# DE-080717.net
KiCad netlist of a schematic drawn in Altium Designer
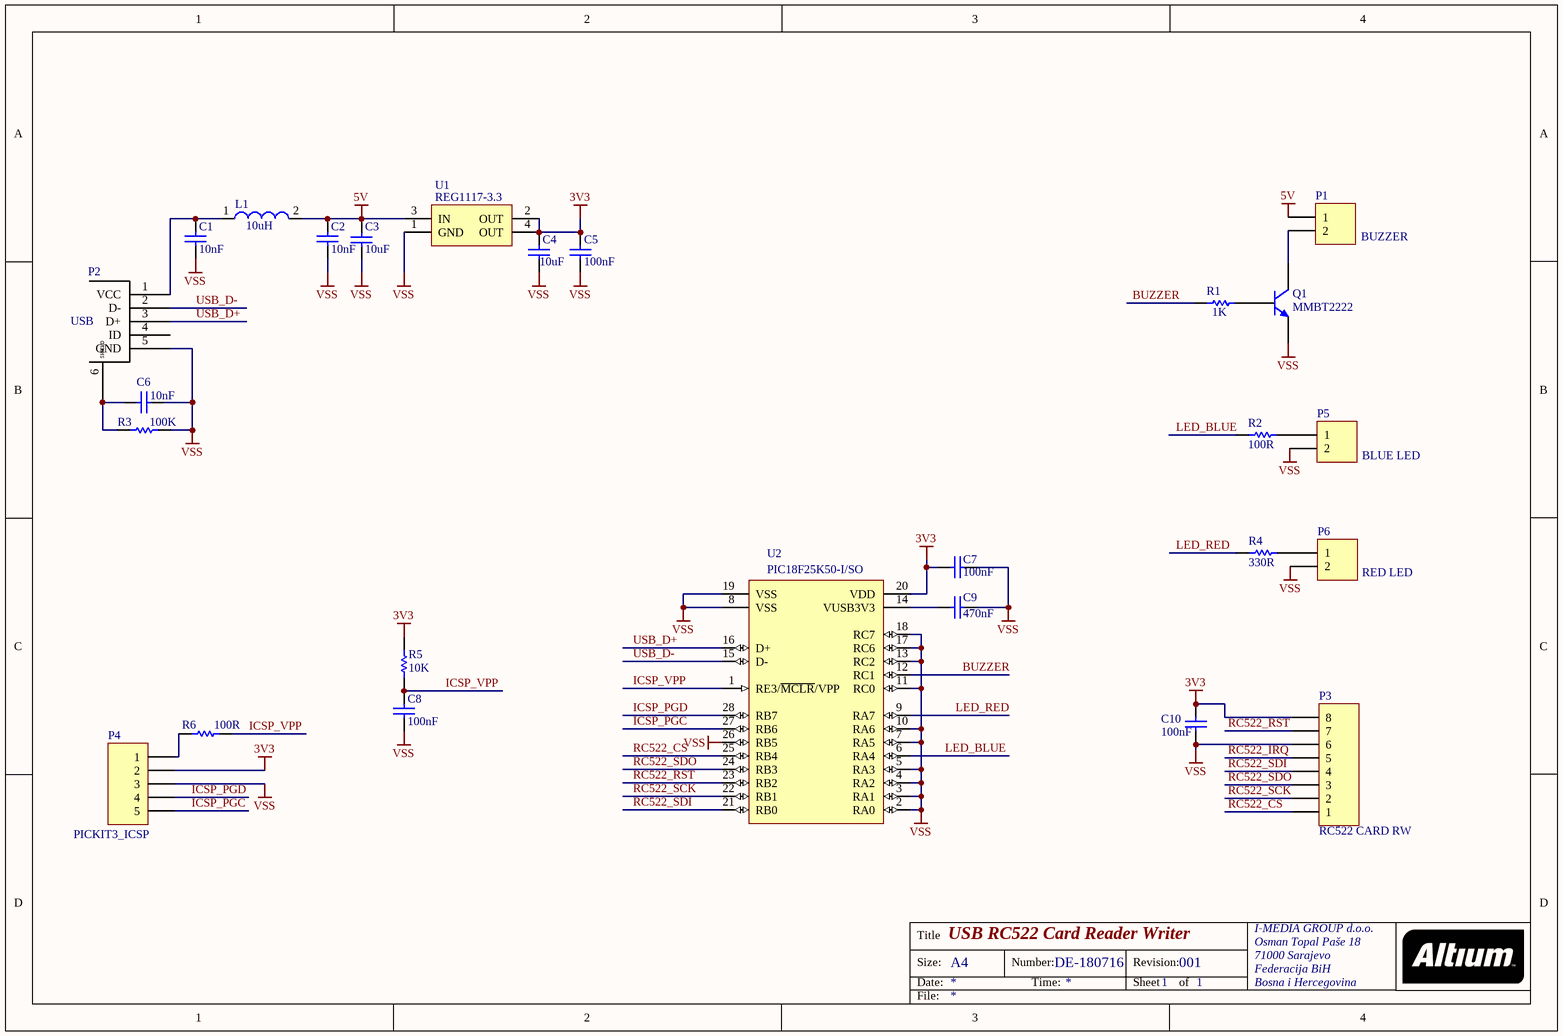
[diagram p0: DE-080717.SchDoc]

(export (version "E")
  (design (tool "Eeschema 10.0.6"))
  (components
    (comp (ref "C1")
      (value "10nF")
      (footprint "0603")
      (description "Ceramic Chip Capacitor - Standard")
      (fields (field (name "PUBLISHER") "Altium Limited"))
      (libsource (lib "USB_RC522_CARD_RW") (part "C0603"))
    )
    (comp (ref "C2")
      (value "10nF")
      (footprint "0603")
      (description "Ceramic Chip Capacitor - Standard")
      (fields (field (name "PUBLISHER") "Altium Limited"))
      (libsource (lib "USB_RC522_CARD_RW") (part "C0603"))
    )
    (comp (ref "C3")
      (value "10uF")
      (footprint "0805")
      (description "Ceramic Chip Capacitor - Standard")
      (fields (field (name "PUBLISHER") "Altium Limited"))
      (libsource (lib "USB_RC522_CARD_RW") (part "C0805"))
    )
    (comp (ref "C4")
      (value "10uF")
      (footprint "0805")
      (description "Ceramic Chip Capacitor - Standard")
      (fields (field (name "PUBLISHER") "Altium Limited"))
      (libsource (lib "USB_RC522_CARD_RW") (part "C0805"))
    )
    (comp (ref "C5")
      (value "100nF")
      (footprint "0603")
      (description "Ceramic Chip Capacitor - Standard")
      (fields (field (name "PUBLISHER") "Altium Limited"))
      (libsource (lib "USB_RC522_CARD_RW") (part "C0603"))
    )
    (comp (ref "C6")
      (value "10nF")
      (footprint "0603")
      (description "Ceramic Chip Capacitor - Standard")
      (fields (field (name "PUBLISHER") "Altium Limited"))
      (libsource (lib "USB_RC522_CARD_RW") (part "C0603"))
    )
    (comp (ref "C7")
      (value "100nF")
      (footprint "0603")
      (description "Ceramic Chip Capacitor - Standard")
      (fields (field (name "PUBLISHER") "Altium Limited"))
      (libsource (lib "USB_RC522_CARD_RW") (part "C0603"))
    )
    (comp (ref "C8")
      (value "100nF")
      (footprint "0603")
      (description "Ceramic Chip Capacitor - Standard")
      (fields (field (name "PUBLISHER") "Altium Limited"))
      (libsource (lib "USB_RC522_CARD_RW") (part "C0603"))
    )
    (comp (ref "C9")
      (value "470nF")
      (footprint "0805")
      (description "Ceramic Chip Capacitor - Standard")
      (fields (field (name "PUBLISHER") "Altium Limited"))
      (libsource (lib "USB_RC522_CARD_RW") (part "C0805"))
    )
    (comp (ref "C10")
      (value "100nF")
      (footprint "0603")
      (description "Ceramic Chip Capacitor - Standard")
      (fields (field (name "PUBLISHER") "Altium Limited"))
      (libsource (lib "USB_RC522_CARD_RW") (part "C0603"))
    )
    (comp (ref "L1")
      (value "10uH")
      (footprint "SMD-0805")
      (description "SMD-Multilayer Inductor WE-MI, L = 8.20 µH")
      (libsource (lib "USB_RC522_CARD_RW") (part "744790282"))
    )
    (comp (ref "P1")
      (value "BUZZER")
      (footprint "HDR1X2")
      (description "Header, 2-Pin")
      (fields (field (name "PUBLISHER") "Altium Limited"))
      (libsource (lib "USB_RC522_CARD_RW") (part "Header 2"))
    )
    (comp (ref "P2")
      (value "USB")
      (footprint "USB mini B")
      (description "USB connector B mini")
      (libsource (lib "USB_RC522_CARD_RW") (part "USB mini B"))
    )
    (comp (ref "P3")
      (value "RC522 CARD RW")
      (footprint "HDR1X8")
      (description "Header, 8-Pin")
      (fields (field (name "PUBLISHER") "Altium Limited"))
      (libsource (lib "USB_RC522_CARD_RW") (part "Header 8"))
    )
    (comp (ref "P4")
      (value "PICKIT3_ICSP")
      (footprint "HDR1X5")
      (description "Header, 5-Pin")
      (fields (field (name "PUBLISHER") "Altium Limited"))
      (libsource (lib "USB_RC522_CARD_RW") (part "Header 5"))
    )
    (comp (ref "P5")
      (value "BLUE LED")
      (footprint "HDR1X2")
      (description "Header, 2-Pin")
      (fields (field (name "PUBLISHER") "Altium Limited"))
      (libsource (lib "USB_RC522_CARD_RW") (part "Header 2"))
    )
    (comp (ref "P6")
      (value "RED LED")
      (footprint "HDR1X2")
      (description "Header, 2-Pin")
      (fields (field (name "PUBLISHER") "Altium Limited"))
      (libsource (lib "USB_RC522_CARD_RW") (part "Header 2"))
    )
    (comp (ref "Q1")
      (value "MMBT2222")
      (footprint "SOT23_N")
      (description "NPN General-purpose Transistor")
      (fields (field (name "PUBLISHER") "Altium Limited"))
      (libsource (lib "USB_RC522_CARD_RW") (part "BC817"))
    )
    (comp (ref "R1")
      (value "1K")
      (footprint "ERA-0603")
      (fields (field (name "PUBLISHER") "Altium Limited"))
      (libsource (lib "USB_RC522_CARD_RW") (part "ERAV"))
    )
    (comp (ref "R2")
      (value "100R")
      (footprint "ERA-0603")
      (fields (field (name "PUBLISHER") "Altium Limited"))
      (libsource (lib "USB_RC522_CARD_RW") (part "ERAV"))
    )
    (comp (ref "R3")
      (value "100K")
      (footprint "ERA-0603")
      (fields (field (name "PUBLISHER") "Altium Limited"))
      (libsource (lib "USB_RC522_CARD_RW") (part "ERAV"))
    )
    (comp (ref "R4")
      (value "330R")
      (footprint "ERA-0603")
      (fields (field (name "PUBLISHER") "Altium Limited"))
      (libsource (lib "USB_RC522_CARD_RW") (part "ERAV"))
    )
    (comp (ref "R5")
      (value "10K")
      (footprint "ERA-0603")
      (fields (field (name "PUBLISHER") "Altium Limited"))
      (libsource (lib "USB_RC522_CARD_RW") (part "ERAV"))
    )
    (comp (ref "R6")
      (value "100R")
      (footprint "ERA-0603")
      (fields (field (name "PUBLISHER") "Altium Limited"))
      (libsource (lib "USB_RC522_CARD_RW") (part "ERAV"))
    )
    (comp (ref "U1")
      (value "REG1117-3.3")
      (footprint "ZZ311")
      (description "800mA and 1A Low Dropout Positive Regulator 2.85V, 3.3V, 5V, and Adjustable")
      (fields (field (name "PUBLISHER") "Altium Limited"))
      (libsource (lib "USB_RC522_CARD_RW") (part "REG1117-3.3"))
    )
    (comp (ref "U2")
      (value "PIC18F25K50-I/SO")
      (footprint "MCHP-SOIC-SO28_N")
      (fields (field (name "MANUFACTURER") "Microchip"))
      (libsource (lib "Microchip PIC18") (part "PIC18F25K50-I/SO"))
    )
  )
  (nets
    (net (code "1") (name "/BUZZER") (class "Default")
      (node (ref "R1") (pin "1") (pinfunction "1_1") (pintype "passive"))
      (node (ref "U2") (pin "12") (pinfunction "RC1_12") (pintype "bidirectional"))
    )
    (net (code "2") (name "/ICSP_PGC") (class "Default")
      (node (ref "P4") (pin "5") (pinfunction "5_5") (pintype "passive"))
      (node (ref "U2") (pin "27") (pinfunction "RB6_27") (pintype "bidirectional"))
    )
    (net (code "3") (name "/ICSP_PGD") (class "Default")
      (node (ref "P4") (pin "4") (pinfunction "4_4") (pintype "passive"))
      (node (ref "U2") (pin "28") (pinfunction "RB7_28") (pintype "bidirectional"))
    )
    (net (code "4") (name "/ICSP_VPP") (class "Default")
      (node (ref "C8") (pin "1") (pinfunction "1_1") (pintype "passive"))
      (node (ref "R5") (pin "1") (pinfunction "1_1") (pintype "passive"))
      (node (ref "R6") (pin "1") (pinfunction "1_1") (pintype "passive"))
      (node (ref "U2") (pin "1") (pinfunction "RE3/~{MCLR}/VPP_1") (pintype "input"))
    )
    (net (code "5") (name "/LED_BLUE") (class "Default")
      (node (ref "R2") (pin "1") (pinfunction "1_1") (pintype "passive"))
      (node (ref "U2") (pin "6") (pinfunction "RA4_6") (pintype "bidirectional"))
    )
    (net (code "6") (name "/LED_RED") (class "Default")
      (node (ref "R4") (pin "1") (pinfunction "1_1") (pintype "passive"))
      (node (ref "U2") (pin "9") (pinfunction "RA7_9") (pintype "bidirectional"))
    )
    (net (code "7") (name "/RC522_CS") (class "Default")
      (node (ref "P3") (pin "1") (pinfunction "1_1") (pintype "passive"))
      (node (ref "U2") (pin "25") (pinfunction "RB4_25") (pintype "bidirectional"))
    )
    (net (code "8") (name "/RC522_IRQ") (class "Default")
      (node (ref "P3") (pin "5") (pinfunction "5_5") (pintype "passive"))
    )
    (net (code "9") (name "/RC522_RST") (class "Default")
      (node (ref "P3") (pin "7") (pinfunction "7_7") (pintype "passive"))
      (node (ref "U2") (pin "23") (pinfunction "RB2_23") (pintype "bidirectional"))
    )
    (net (code "10") (name "/RC522_SCK") (class "Default")
      (node (ref "P3") (pin "2") (pinfunction "2_2") (pintype "passive"))
      (node (ref "U2") (pin "22") (pinfunction "RB1_22") (pintype "bidirectional"))
    )
    (net (code "11") (name "/RC522_SDI") (class "Default")
      (node (ref "P3") (pin "4") (pinfunction "4_4") (pintype "passive"))
      (node (ref "U2") (pin "21") (pinfunction "RB0_21") (pintype "bidirectional"))
    )
    (net (code "12") (name "/RC522_SDO") (class "Default")
      (node (ref "P3") (pin "3") (pinfunction "3_3") (pintype "passive"))
      (node (ref "U2") (pin "24") (pinfunction "RB3_24") (pintype "bidirectional"))
    )
    (net (code "13") (name "/USB_D+") (class "Default")
      (node (ref "P2") (pin "3") (pinfunction "D+_3") (pintype "passive"))
      (node (ref "U2") (pin "16") (pinfunction "D+_16") (pintype "bidirectional"))
    )
    (net (code "14") (name "/USB_D-") (class "Default")
      (node (ref "P2") (pin "2") (pinfunction "D-_2") (pintype "passive"))
      (node (ref "U2") (pin "15") (pinfunction "D-_15") (pintype "bidirectional"))
    )
    (net (code "15") (name "3V3") (class "Default")
      (node (ref "C10") (pin "1") (pinfunction "1_1") (pintype "passive"))
      (node (ref "C4") (pin "2") (pinfunction "2_2") (pintype "passive"))
      (node (ref "C5") (pin "2") (pinfunction "2_2") (pintype "passive"))
      (node (ref "C7") (pin "2") (pinfunction "2_2") (pintype "passive"))
      (node (ref "P3") (pin "8") (pinfunction "8_8") (pintype "passive"))
      (node (ref "P4") (pin "2") (pinfunction "2_2") (pintype "passive"))
      (node (ref "R5") (pin "2") (pinfunction "2_2") (pintype "passive"))
      (node (ref "U1") (pin "2") (pinfunction "OUT_2") (pintype "power_in"))
      (node (ref "U1") (pin "4") (pinfunction "OUT_4") (pintype "power_in"))
      (node (ref "U2") (pin "20") (pinfunction "VDD_20") (pintype "power_in"))
    )
    (net (code "16") (name "5V") (class "Default")
      (node (ref "C2") (pin "1") (pinfunction "1_1") (pintype "passive"))
      (node (ref "C3") (pin "1") (pinfunction "1_1") (pintype "passive"))
      (node (ref "L1") (pin "2") (pinfunction "2_2") (pintype "passive"))
      (node (ref "P1") (pin "1") (pinfunction "1_1") (pintype "passive"))
      (node (ref "U1") (pin "3") (pinfunction "IN_3") (pintype "power_in"))
    )
    (net (code "17") (name "Net-(P2-SHIELD)") (class "Default")
      (node (ref "C6") (pin "1") (pinfunction "1_1") (pintype "passive"))
      (node (ref "P2") (pin "6") (pinfunction "SHIELD_6") (pintype "passive"))
      (node (ref "R3") (pin "2") (pinfunction "2_2") (pintype "passive"))
    )
    (net (code "18") (name "Net-(P2-VCC)") (class "Default")
      (node (ref "C1") (pin "1") (pinfunction "1_1") (pintype "passive"))
      (node (ref "L1") (pin "1") (pinfunction "1_1") (pintype "passive"))
      (node (ref "P2") (pin "1") (pinfunction "VCC_1") (pintype "passive"))
    )
    (net (code "19") (name "Net-(P4-Pad1)") (class "Default")
      (node (ref "P4") (pin "1") (pinfunction "1_1") (pintype "passive"))
      (node (ref "R6") (pin "2") (pinfunction "2_2") (pintype "passive"))
    )
    (net (code "20") (name "Net-(P5-Pad1)") (class "Default")
      (node (ref "P5") (pin "1") (pinfunction "1_1") (pintype "passive"))
      (node (ref "R2") (pin "2") (pinfunction "2_2") (pintype "passive"))
    )
    (net (code "21") (name "Net-(P6-Pad1)") (class "Default")
      (node (ref "P6") (pin "1") (pinfunction "1_1") (pintype "passive"))
      (node (ref "R4") (pin "2") (pinfunction "2_2") (pintype "passive"))
    )
    (net (code "22") (name "Net-(Q1-B)") (class "Default")
      (node (ref "Q1") (pin "1") (pinfunction "B_1") (pintype "passive"))
      (node (ref "R1") (pin "2") (pinfunction "2_2") (pintype "passive"))
    )
    (net (code "23") (name "Net-(Q1-C)") (class "Default")
      (node (ref "P1") (pin "2") (pinfunction "2_2") (pintype "passive"))
      (node (ref "Q1") (pin "3") (pinfunction "C_3") (pintype "passive"))
    )
    (net (code "24") (name "Net-(U2-VUSB3V3)") (class "Default")
      (node (ref "C9") (pin "2") (pinfunction "2_2") (pintype "passive"))
      (node (ref "U2") (pin "14") (pinfunction "VUSB3V3_14") (pintype "power_in"))
    )
    (net (code "25") (name "VSS") (class "Default")
      (node (ref "C1") (pin "2") (pinfunction "2_2") (pintype "passive"))
      (node (ref "C10") (pin "2") (pinfunction "2_2") (pintype "passive"))
      (node (ref "C2") (pin "2") (pinfunction "2_2") (pintype "passive"))
      (node (ref "C3") (pin "2") (pinfunction "2_2") (pintype "passive"))
      (node (ref "C4") (pin "1") (pinfunction "1_1") (pintype "passive"))
      (node (ref "C5") (pin "1") (pinfunction "1_1") (pintype "passive"))
      (node (ref "C6") (pin "2") (pinfunction "2_2") (pintype "passive"))
      (node (ref "C7") (pin "1") (pinfunction "1_1") (pintype "passive"))
      (node (ref "C8") (pin "2") (pinfunction "2_2") (pintype "passive"))
      (node (ref "C9") (pin "1") (pinfunction "1_1") (pintype "passive"))
      (node (ref "P2") (pin "5") (pinfunction "GND_5") (pintype "passive"))
      (node (ref "P3") (pin "6") (pinfunction "6_6") (pintype "passive"))
      (node (ref "P4") (pin "3") (pinfunction "3_3") (pintype "passive"))
      (node (ref "P5") (pin "2") (pinfunction "2_2") (pintype "passive"))
      (node (ref "P6") (pin "2") (pinfunction "2_2") (pintype "passive"))
      (node (ref "Q1") (pin "2") (pinfunction "E_2") (pintype "passive"))
      (node (ref "R3") (pin "1") (pinfunction "1_1") (pintype "passive"))
      (node (ref "U1") (pin "1") (pinfunction "GND_1") (pintype "power_in"))
      (node (ref "U2") (pin "10") (pinfunction "RA6_10") (pintype "bidirectional"))
      (node (ref "U2") (pin "11") (pinfunction "RC0_11") (pintype "bidirectional"))
      (node (ref "U2") (pin "13") (pinfunction "RC2_13") (pintype "bidirectional"))
      (node (ref "U2") (pin "17") (pinfunction "RC6_17") (pintype "bidirectional"))
      (node (ref "U2") (pin "18") (pinfunction "RC7_18") (pintype "bidirectional"))
      (node (ref "U2") (pin "19") (pinfunction "VSS_19") (pintype "power_in"))
      (node (ref "U2") (pin "2") (pinfunction "RA0_2") (pintype "bidirectional"))
      (node (ref "U2") (pin "26") (pinfunction "RB5_26") (pintype "bidirectional"))
      (node (ref "U2") (pin "3") (pinfunction "RA1_3") (pintype "bidirectional"))
      (node (ref "U2") (pin "4") (pinfunction "RA2_4") (pintype "bidirectional"))
      (node (ref "U2") (pin "5") (pinfunction "RA3_5") (pintype "bidirectional"))
      (node (ref "U2") (pin "7") (pinfunction "RA5_7") (pintype "bidirectional"))
      (node (ref "U2") (pin "8") (pinfunction "VSS_8") (pintype "power_in"))
    )
    (net (code "26") (name "unconnected-(P2-ID-Pad4)") (class "Default")
      (node (ref "P2") (pin "4") (pinfunction "ID_4") (pintype "passive"))
    )
  )
)
